# Public_CPU_IO.net
KiCad netlist of a schematic drawn in Altium Designer
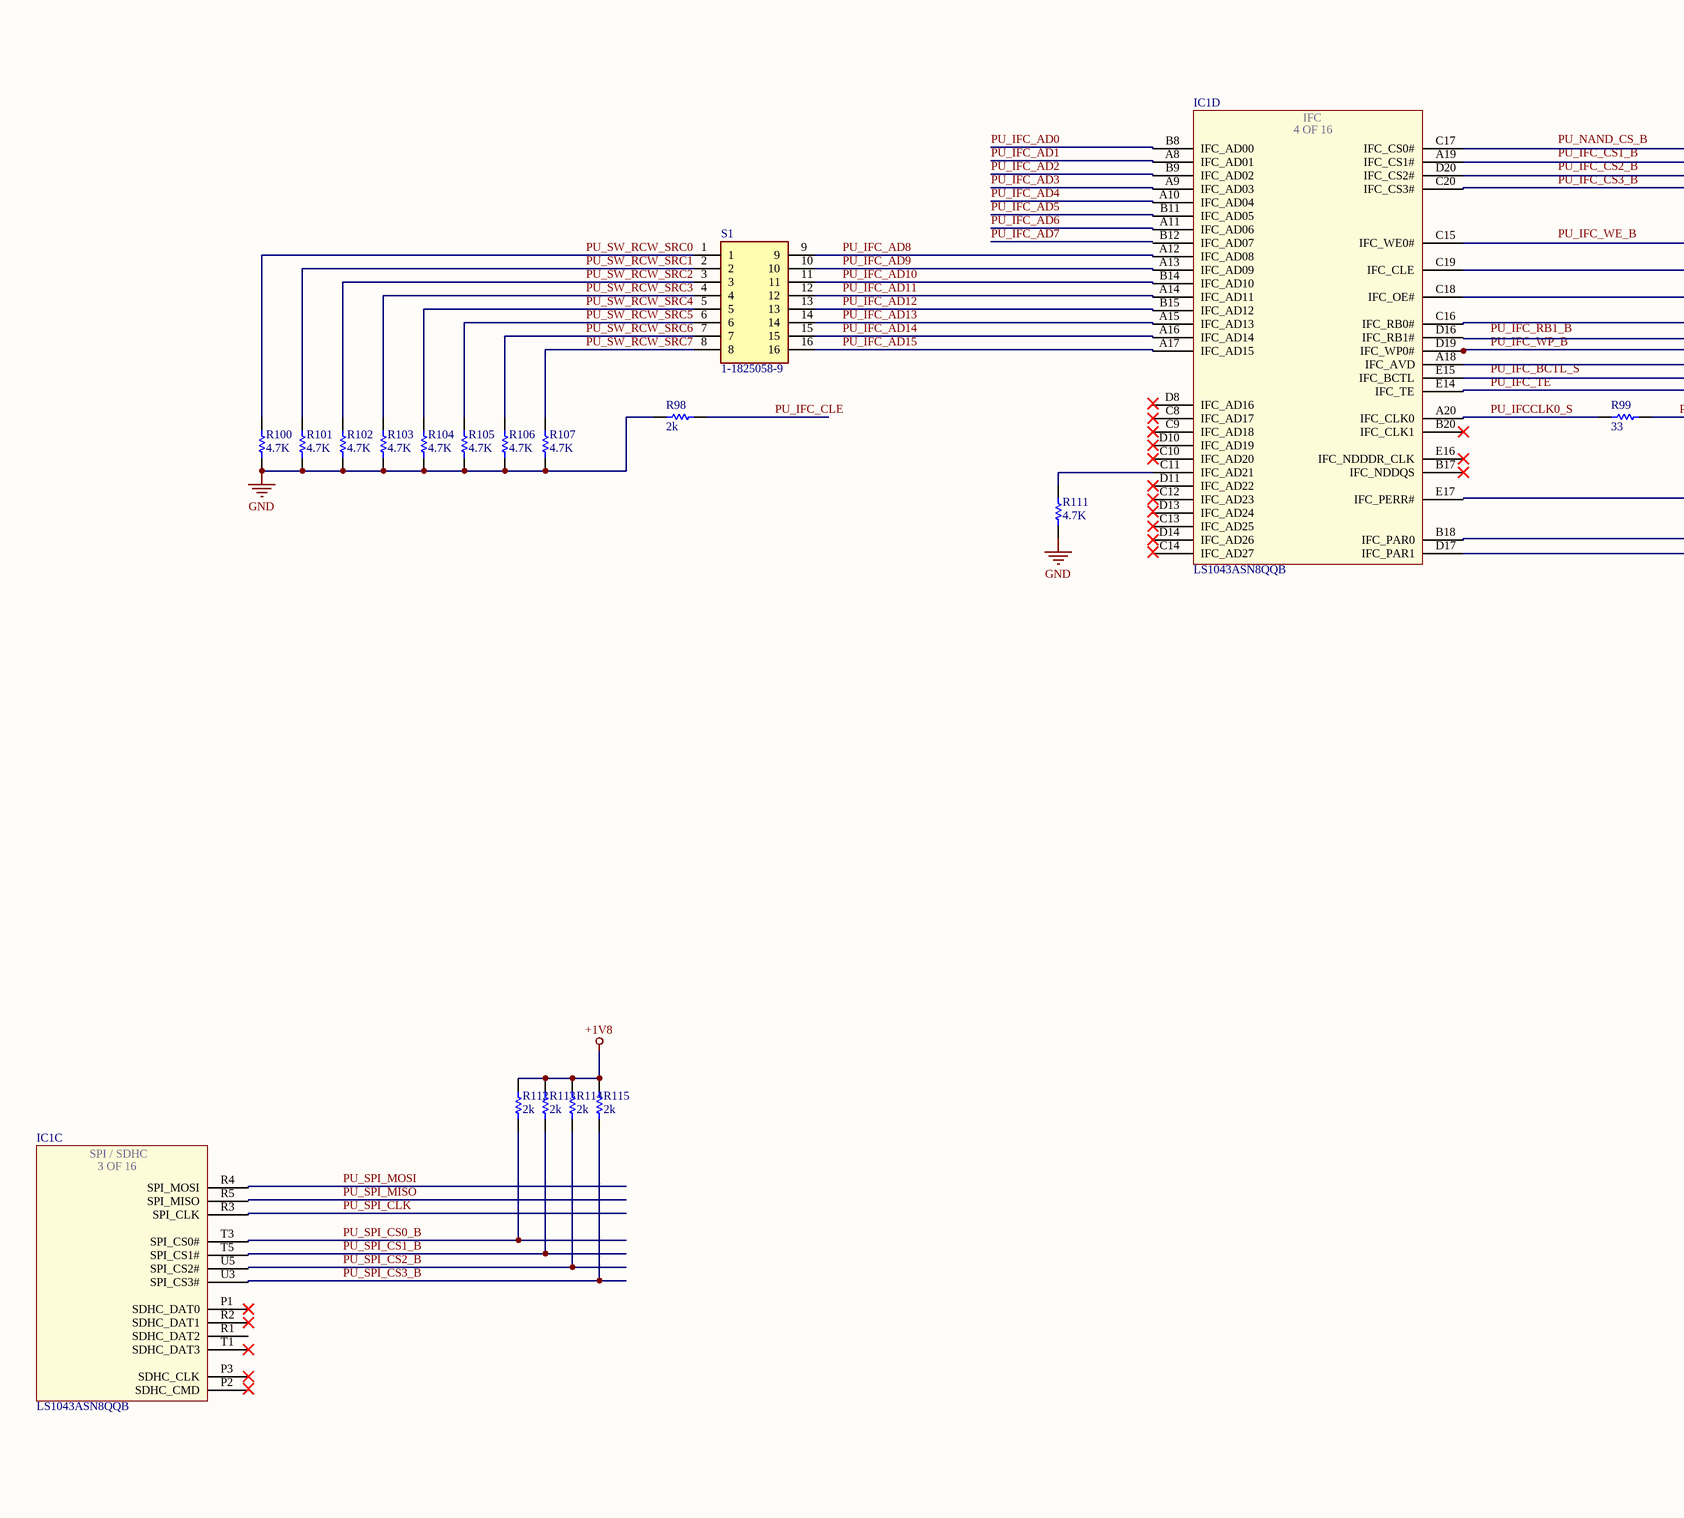
[diagram p0: Public_CPU_IO.SchDoc, left]
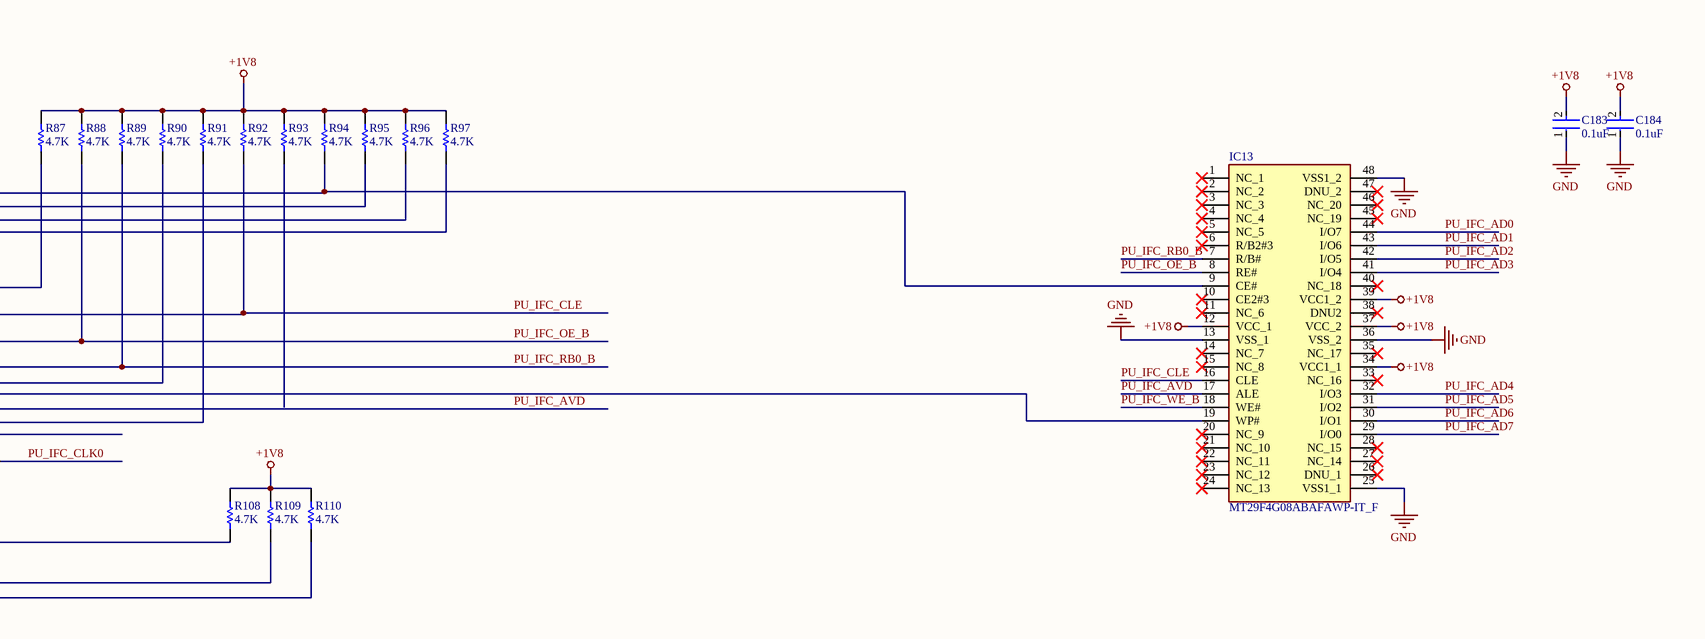
[diagram p1: Public_CPU_IO.SchDoc, right]

(export (version "E")
  (design (tool "Eeschema 10.0.6"))
  (components
    (comp (ref "C183")
      (value "0.1uF")
      (footprint "FP-GRM15-MFG")
      (description "CAP CER 0.1UF 16V X7R 0402")
      (fields (field (name "MANUFACTURER PART NUMBER") "GRM155R71C104KA88D") (field (name "TOLERANCE") "10%"))
      (libsource (lib "Altium Content Vault") (part "236180d848d6139a670b325ea6854c9"))
    )
    (comp (ref "C184")
      (value "0.1uF")
      (footprint "FP-GRM15-MFG")
      (description "CAP CER 0.1UF 16V X7R 0402")
      (fields (field (name "MANUFACTURER PART NUMBER") "GRM155R71C104KA88D") (field (name "TOLERANCE") "10%"))
      (libsource (lib "Altium Content Vault") (part "236180d848d6139a670b325ea6854c9"))
    )
    (comp (ref "IC1")
      (value "LS1043ASN8QQB")
      (footprint "SamacSys:BGA780C80P28X28_2300X2300X261")
      (description "Integrated Circuit")
      (fields (field (name "MOUSER PART NUMBER") "771-LS1043ASN8QQB"))
      (libsource (lib "SamacSys") (part "LS1043ASN8QQB"))
    )
    (comp (ref "IC13")
      (value "MT29F4G08ABAFAWP-IT_F")
      (footprint "SamacSys:SOP50P2000X120-48N")
      (description "Integrated Circuit")
      (fields
        (field (name "MANUFACTURER_PART_NUMBER") "MT29F4G08ABAFAWP-IT:F")
        (field (name "MOUSER PART NUMBER") "340-371016-TRAY")
      )
      (libsource (lib "*") (part "MT29F4G08ABAFAWP-IT_F"))
    )
    (comp (ref "R87")
      (value "4.7K")
      (footprint "RESC1005X40X25LL05T05")
      (description "Chip Resistor, 4.7 KOhm, +/- 1%, 0.1 W, -55 to 155 degC, 0402 (1005 Metric), RoHS, Tape and Reel")
      (fields (field (name "TOLERANCE") "1%") (field (name "PARTNUMBER") "ERJ-2RKF4701X"))
      (libsource (lib "Altium Content Vault") (part "RES-2"))
    )
    (comp (ref "R88")
      (value "4.7K")
      (footprint "RESC1005X40X25LL05T05")
      (description "Chip Resistor, 4.7 KOhm, +/- 1%, 0.1 W, -55 to 155 degC, 0402 (1005 Metric), RoHS, Tape and Reel")
      (fields (field (name "TOLERANCE") "1%") (field (name "PARTNUMBER") "ERJ-2RKF4701X"))
      (libsource (lib "Altium Content Vault") (part "RES-2"))
    )
    (comp (ref "R89")
      (value "4.7K")
      (footprint "RESC1005X40X25LL05T05")
      (description "Chip Resistor, 4.7 KOhm, +/- 1%, 0.1 W, -55 to 155 degC, 0402 (1005 Metric), RoHS, Tape and Reel")
      (fields (field (name "TOLERANCE") "1%") (field (name "PARTNUMBER") "ERJ-2RKF4701X"))
      (libsource (lib "Altium Content Vault") (part "RES-2"))
    )
    (comp (ref "R90")
      (value "4.7K")
      (footprint "RESC1005X40X25LL05T05")
      (description "Chip Resistor, 4.7 KOhm, +/- 1%, 0.1 W, -55 to 155 degC, 0402 (1005 Metric), RoHS, Tape and Reel")
      (fields (field (name "TOLERANCE") "1%") (field (name "PARTNUMBER") "ERJ-2RKF4701X"))
      (libsource (lib "Altium Content Vault") (part "RES-2"))
    )
    (comp (ref "R91")
      (value "4.7K")
      (footprint "RESC1005X40X25LL05T05")
      (description "Chip Resistor, 4.7 KOhm, +/- 1%, 0.1 W, -55 to 155 degC, 0402 (1005 Metric), RoHS, Tape and Reel")
      (fields (field (name "TOLERANCE") "1%") (field (name "PARTNUMBER") "ERJ-2RKF4701X"))
      (libsource (lib "Altium Content Vault") (part "RES-2"))
    )
    (comp (ref "R92")
      (value "4.7K")
      (footprint "RESC1005X40X25LL05T05")
      (description "Chip Resistor, 4.7 KOhm, +/- 1%, 0.1 W, -55 to 155 degC, 0402 (1005 Metric), RoHS, Tape and Reel")
      (fields (field (name "TOLERANCE") "1%") (field (name "PARTNUMBER") "ERJ-2RKF4701X"))
      (libsource (lib "Altium Content Vault") (part "RES-2"))
    )
    (comp (ref "R93")
      (value "4.7K")
      (footprint "RESC1005X40X25LL05T05")
      (description "Chip Resistor, 4.7 KOhm, +/- 1%, 0.1 W, -55 to 155 degC, 0402 (1005 Metric), RoHS, Tape and Reel")
      (fields (field (name "TOLERANCE") "1%") (field (name "PARTNUMBER") "ERJ-2RKF4701X"))
      (libsource (lib "Altium Content Vault") (part "RES-2"))
    )
    (comp (ref "R94")
      (value "4.7K")
      (footprint "RESC1005X40X25LL05T05")
      (description "Chip Resistor, 4.7 KOhm, +/- 1%, 0.1 W, -55 to 155 degC, 0402 (1005 Metric), RoHS, Tape and Reel")
      (fields (field (name "TOLERANCE") "1%") (field (name "PARTNUMBER") "ERJ-2RKF4701X"))
      (libsource (lib "Altium Content Vault") (part "RES-2"))
    )
    (comp (ref "R95")
      (value "4.7K")
      (footprint "RESC1005X40X25LL05T05")
      (description "Chip Resistor, 4.7 KOhm, +/- 1%, 0.1 W, -55 to 155 degC, 0402 (1005 Metric), RoHS, Tape and Reel")
      (fields (field (name "TOLERANCE") "1%") (field (name "PARTNUMBER") "ERJ-2RKF4701X"))
      (libsource (lib "Altium Content Vault") (part "RES-2"))
    )
    (comp (ref "R96")
      (value "4.7K")
      (footprint "RESC1005X40X25LL05T05")
      (description "Chip Resistor, 4.7 KOhm, +/- 1%, 0.1 W, -55 to 155 degC, 0402 (1005 Metric), RoHS, Tape and Reel")
      (fields (field (name "TOLERANCE") "1%") (field (name "PARTNUMBER") "ERJ-2RKF4701X"))
      (libsource (lib "Altium Content Vault") (part "RES-2"))
    )
    (comp (ref "R97")
      (value "4.7K")
      (footprint "RESC1005X40X25LL05T05")
      (description "Chip Resistor, 4.7 KOhm, +/- 1%, 0.1 W, -55 to 155 degC, 0402 (1005 Metric), RoHS, Tape and Reel")
      (fields (field (name "TOLERANCE") "1%") (field (name "PARTNUMBER") "ERJ-2RKF4701X"))
      (libsource (lib "Altium Content Vault") (part "RES-2"))
    )
    (comp (ref "R98")
      (value "2k")
      (footprint "RESC1005X40X25NL05T05")
      (description "Chip Resistor, 2 KOhm, +/- 1%, 100 mW, -55 to 155 degC, 0402 (1005 Metric), RoHS, Tape and Reel")
      (fields (field (name "MANUFACTURER") "Basic Passives") (field (name "TOLERANCE") "1%"))
      (libsource (lib "Altium Content Vault") (part "RES-2"))
    )
    (comp (ref "R99")
      (value "33")
      (footprint "RESC1005X40X25LL05T05")
      (fields (field (name "MANUFACTURER") "Panasonic") (field (name "PART NUMBER") "ERJ2RKF33R0X"))
      (libsource (lib "Altium Content Vault") (part "RES"))
    )
    (comp (ref "R100")
      (value "4.7K")
      (footprint "RESC1005X40X25LL05T05")
      (description "Chip Resistor, 4.7 KOhm, +/- 1%, 0.1 W, -55 to 155 degC, 0402 (1005 Metric), RoHS, Tape and Reel")
      (fields (field (name "TOLERANCE") "1%") (field (name "PARTNUMBER") "ERJ-2RKF4701X"))
      (libsource (lib "Altium Content Vault") (part "RES-2"))
    )
    (comp (ref "R101")
      (value "4.7K")
      (footprint "RESC1005X40X25LL05T05")
      (description "Chip Resistor, 4.7 KOhm, +/- 1%, 0.1 W, -55 to 155 degC, 0402 (1005 Metric), RoHS, Tape and Reel")
      (fields (field (name "TOLERANCE") "1%") (field (name "PARTNUMBER") "ERJ-2RKF4701X"))
      (libsource (lib "Altium Content Vault") (part "RES-2"))
    )
    (comp (ref "R102")
      (value "4.7K")
      (footprint "RESC1005X40X25LL05T05")
      (description "Chip Resistor, 4.7 KOhm, +/- 1%, 0.1 W, -55 to 155 degC, 0402 (1005 Metric), RoHS, Tape and Reel")
      (fields (field (name "TOLERANCE") "1%") (field (name "PARTNUMBER") "ERJ-2RKF4701X"))
      (libsource (lib "Altium Content Vault") (part "RES-2"))
    )
    (comp (ref "R103")
      (value "4.7K")
      (footprint "RESC1005X40X25LL05T05")
      (description "Chip Resistor, 4.7 KOhm, +/- 1%, 0.1 W, -55 to 155 degC, 0402 (1005 Metric), RoHS, Tape and Reel")
      (fields (field (name "TOLERANCE") "1%") (field (name "PARTNUMBER") "ERJ-2RKF4701X"))
      (libsource (lib "Altium Content Vault") (part "RES-2"))
    )
    (comp (ref "R104")
      (value "4.7K")
      (footprint "RESC1005X40X25LL05T05")
      (description "Chip Resistor, 4.7 KOhm, +/- 1%, 0.1 W, -55 to 155 degC, 0402 (1005 Metric), RoHS, Tape and Reel")
      (fields (field (name "TOLERANCE") "1%") (field (name "PARTNUMBER") "ERJ-2RKF4701X"))
      (libsource (lib "Altium Content Vault") (part "RES-2"))
    )
    (comp (ref "R105")
      (value "4.7K")
      (footprint "RESC1005X40X25LL05T05")
      (description "Chip Resistor, 4.7 KOhm, +/- 1%, 0.1 W, -55 to 155 degC, 0402 (1005 Metric), RoHS, Tape and Reel")
      (fields (field (name "TOLERANCE") "1%") (field (name "PARTNUMBER") "ERJ-2RKF4701X"))
      (libsource (lib "Altium Content Vault") (part "RES-2"))
    )
    (comp (ref "R106")
      (value "4.7K")
      (footprint "RESC1005X40X25LL05T05")
      (description "Chip Resistor, 4.7 KOhm, +/- 1%, 0.1 W, -55 to 155 degC, 0402 (1005 Metric), RoHS, Tape and Reel")
      (fields (field (name "TOLERANCE") "1%") (field (name "PARTNUMBER") "ERJ-2RKF4701X"))
      (libsource (lib "Altium Content Vault") (part "RES-2"))
    )
    (comp (ref "R107")
      (value "4.7K")
      (footprint "RESC1005X40X25LL05T05")
      (description "Chip Resistor, 4.7 KOhm, +/- 1%, 0.1 W, -55 to 155 degC, 0402 (1005 Metric), RoHS, Tape and Reel")
      (fields (field (name "TOLERANCE") "1%") (field (name "PARTNUMBER") "ERJ-2RKF4701X"))
      (libsource (lib "Altium Content Vault") (part "RES-2"))
    )
    (comp (ref "R108")
      (value "4.7K")
      (footprint "RESC1005X40X25LL05T05")
      (description "Chip Resistor, 4.7 KOhm, +/- 1%, 0.1 W, -55 to 155 degC, 0402 (1005 Metric), RoHS, Tape and Reel")
      (fields (field (name "TOLERANCE") "1%") (field (name "PARTNUMBER") "ERJ-2RKF4701X"))
      (libsource (lib "Altium Content Vault") (part "RES-2"))
    )
    (comp (ref "R109")
      (value "4.7K")
      (footprint "RESC1005X40X25LL05T05")
      (description "Chip Resistor, 4.7 KOhm, +/- 1%, 0.1 W, -55 to 155 degC, 0402 (1005 Metric), RoHS, Tape and Reel")
      (fields (field (name "TOLERANCE") "1%") (field (name "PARTNUMBER") "ERJ-2RKF4701X"))
      (libsource (lib "Altium Content Vault") (part "RES-2"))
    )
    (comp (ref "R110")
      (value "4.7K")
      (footprint "RESC1005X40X25LL05T05")
      (description "Chip Resistor, 4.7 KOhm, +/- 1%, 0.1 W, -55 to 155 degC, 0402 (1005 Metric), RoHS, Tape and Reel")
      (fields (field (name "TOLERANCE") "1%") (field (name "PARTNUMBER") "ERJ-2RKF4701X"))
      (libsource (lib "Altium Content Vault") (part "RES-2"))
    )
    (comp (ref "R111")
      (value "4.7K")
      (footprint "RESC1005X40X25LL05T05")
      (description "Chip Resistor, 4.7 KOhm, +/- 1%, 0.1 W, -55 to 155 degC, 0402 (1005 Metric), RoHS, Tape and Reel")
      (fields (field (name "TOLERANCE") "1%") (field (name "PARTNUMBER") "ERJ-2RKF4701X"))
      (libsource (lib "Altium Content Vault") (part "RES-2"))
    )
    (comp (ref "R112")
      (value "2k")
      (footprint "RESC1005X40X25NL05T05")
      (description "Chip Resistor, 2 KOhm, +/- 1%, 100 mW, -55 to 155 degC, 0402 (1005 Metric), RoHS, Tape and Reel")
      (fields (field (name "MANUFACTURER") "Basic Passives") (field (name "TOLERANCE") "1%"))
      (libsource (lib "Altium Content Vault") (part "RES-2"))
    )
    (comp (ref "R113")
      (value "2k")
      (footprint "RESC1005X40X25NL05T05")
      (description "Chip Resistor, 2 KOhm, +/- 1%, 100 mW, -55 to 155 degC, 0402 (1005 Metric), RoHS, Tape and Reel")
      (fields (field (name "MANUFACTURER") "Basic Passives") (field (name "TOLERANCE") "1%"))
      (libsource (lib "Altium Content Vault") (part "RES-2"))
    )
    (comp (ref "R114")
      (value "2k")
      (footprint "RESC1005X40X25NL05T05")
      (description "Chip Resistor, 2 KOhm, +/- 1%, 100 mW, -55 to 155 degC, 0402 (1005 Metric), RoHS, Tape and Reel")
      (fields (field (name "MANUFACTURER") "Basic Passives") (field (name "TOLERANCE") "1%"))
      (libsource (lib "Altium Content Vault") (part "RES-2"))
    )
    (comp (ref "R115")
      (value "2k")
      (footprint "RESC1005X40X25NL05T05")
      (description "Chip Resistor, 2 KOhm, +/- 1%, 100 mW, -55 to 155 degC, 0402 (1005 Metric), RoHS, Tape and Reel")
      (fields (field (name "MANUFACTURER") "Basic Passives") (field (name "TOLERANCE") "1%"))
      (libsource (lib "Altium Content Vault") (part "RES-2"))
    )
    (comp (ref "S1")
      (value "1-1825058-9")
      (footprint "SamacSys:118250589")
      (description "Switch")
      (libsource (lib "*") (part "1-1825058-9"))
    )
  )
  (nets
    (net (code "1") (name "+1V8") (class "Default")
      (node (ref "C183") (pin "2") (pinfunction "2_2") (pintype "passive"))
      (node (ref "C184") (pin "2") (pinfunction "2_2") (pintype "passive"))
      (node (ref "IC13") (pin "12") (pinfunction "VCC_1_12") (pintype "passive"))
      (node (ref "IC13") (pin "34") (pinfunction "VCC1_1_34") (pintype "passive"))
      (node (ref "IC13") (pin "37") (pinfunction "VCC_2_37") (pintype "passive"))
      (node (ref "IC13") (pin "39") (pinfunction "VCC1_2_39") (pintype "passive"))
      (node (ref "R108") (pin "2") (pinfunction "2_2") (pintype "passive"))
      (node (ref "R109") (pin "2") (pinfunction "2_2") (pintype "passive"))
      (node (ref "R110") (pin "2") (pinfunction "2_2") (pintype "passive"))
      (node (ref "R112") (pin "1") (pinfunction "1_1") (pintype "passive"))
      (node (ref "R113") (pin "1") (pinfunction "1_1") (pintype "passive"))
      (node (ref "R114") (pin "1") (pinfunction "1_1") (pintype "passive"))
      (node (ref "R115") (pin "1") (pinfunction "1_1") (pintype "passive"))
      (node (ref "R87") (pin "2") (pinfunction "2_2") (pintype "passive"))
      (node (ref "R88") (pin "2") (pinfunction "2_2") (pintype "passive"))
      (node (ref "R89") (pin "2") (pinfunction "2_2") (pintype "passive"))
      (node (ref "R90") (pin "2") (pinfunction "2_2") (pintype "passive"))
      (node (ref "R91") (pin "2") (pinfunction "2_2") (pintype "passive"))
      (node (ref "R92") (pin "2") (pinfunction "2_2") (pintype "passive"))
      (node (ref "R93") (pin "2") (pinfunction "2_2") (pintype "passive"))
      (node (ref "R94") (pin "2") (pinfunction "2_2") (pintype "passive"))
      (node (ref "R95") (pin "2") (pinfunction "2_2") (pintype "passive"))
      (node (ref "R96") (pin "2") (pinfunction "2_2") (pintype "passive"))
      (node (ref "R97") (pin "2") (pinfunction "2_2") (pintype "passive"))
    )
    (net (code "2") (name "/PU_IFCCLK0_S") (class "Default")
      (node (ref "IC1") (pin "A20") (pinfunction "IFC_CLK0_A20") (pintype "passive"))
      (node (ref "R99") (pin "1") (pinfunction "1_1") (pintype "passive"))
    )
    (net (code "3") (name "/PU_IFC_AD0") (class "Default")
      (node (ref "IC1") (pin "B8") (pinfunction "IFC_AD00_B8") (pintype "passive"))
      (node (ref "IC13") (pin "44") (pinfunction "I/O7_44") (pintype "passive"))
    )
    (net (code "4") (name "/PU_IFC_AD1") (class "Default")
      (node (ref "IC1") (pin "A8") (pinfunction "IFC_AD01_A8") (pintype "passive"))
      (node (ref "IC13") (pin "43") (pinfunction "I/O6_43") (pintype "passive"))
    )
    (net (code "5") (name "/PU_IFC_AD2") (class "Default")
      (node (ref "IC1") (pin "B9") (pinfunction "IFC_AD02_B9") (pintype "passive"))
      (node (ref "IC13") (pin "42") (pinfunction "I/O5_42") (pintype "passive"))
    )
    (net (code "6") (name "/PU_IFC_AD3") (class "Default")
      (node (ref "IC1") (pin "A9") (pinfunction "IFC_AD03_A9") (pintype "passive"))
      (node (ref "IC13") (pin "41") (pinfunction "I/O4_41") (pintype "passive"))
    )
    (net (code "7") (name "/PU_IFC_AD4") (class "Default")
      (node (ref "IC1") (pin "A10") (pinfunction "IFC_AD04_A10") (pintype "passive"))
      (node (ref "IC13") (pin "32") (pinfunction "I/O3_32") (pintype "passive"))
    )
    (net (code "8") (name "/PU_IFC_AD5") (class "Default")
      (node (ref "IC1") (pin "B11") (pinfunction "IFC_AD05_B11") (pintype "passive"))
      (node (ref "IC13") (pin "31") (pinfunction "I/O2_31") (pintype "passive"))
    )
    (net (code "9") (name "/PU_IFC_AD6") (class "Default")
      (node (ref "IC1") (pin "A11") (pinfunction "IFC_AD06_A11") (pintype "passive"))
      (node (ref "IC13") (pin "30") (pinfunction "I/O1_30") (pintype "passive"))
    )
    (net (code "10") (name "/PU_IFC_AD7") (class "Default")
      (node (ref "IC13") (pin "29") (pinfunction "I/O0_29") (pintype "passive"))
    )
    (net (code "11") (name "/PU_IFC_AD8") (class "Default")
      (node (ref "IC1") (pin "A12") (pinfunction "IFC_AD08_A12") (pintype "passive"))
      (node (ref "S1") (pin "9") (pinfunction "9_9") (pintype "passive"))
    )
    (net (code "12") (name "/PU_IFC_AD9") (class "Default")
      (node (ref "IC1") (pin "A13") (pinfunction "IFC_AD09_A13") (pintype "passive"))
      (node (ref "S1") (pin "10") (pinfunction "10_10") (pintype "passive"))
    )
    (net (code "13") (name "/PU_IFC_AD10") (class "Default")
      (node (ref "IC1") (pin "B14") (pinfunction "IFC_AD10_B14") (pintype "passive"))
      (node (ref "S1") (pin "11") (pinfunction "11_11") (pintype "passive"))
    )
    (net (code "14") (name "/PU_IFC_AD11") (class "Default")
      (node (ref "IC1") (pin "A14") (pinfunction "IFC_AD11_A14") (pintype "passive"))
      (node (ref "S1") (pin "12") (pinfunction "12_12") (pintype "passive"))
    )
    (net (code "15") (name "/PU_IFC_AD12") (class "Default")
      (node (ref "IC1") (pin "B15") (pinfunction "IFC_AD12_B15") (pintype "passive"))
      (node (ref "S1") (pin "13") (pinfunction "13_13") (pintype "passive"))
    )
    (net (code "16") (name "/PU_IFC_AD13") (class "Default")
      (node (ref "IC1") (pin "A15") (pinfunction "IFC_AD13_A15") (pintype "passive"))
      (node (ref "S1") (pin "14") (pinfunction "14_14") (pintype "passive"))
    )
    (net (code "17") (name "/PU_IFC_AD14") (class "Default")
      (node (ref "IC1") (pin "A16") (pinfunction "IFC_AD14_A16") (pintype "passive"))
      (node (ref "S1") (pin "15") (pinfunction "15_15") (pintype "passive"))
    )
    (net (code "18") (name "/PU_IFC_AD15") (class "Default")
      (node (ref "IC1") (pin "A17") (pinfunction "IFC_AD15_A17") (pintype "passive"))
      (node (ref "S1") (pin "16") (pinfunction "16_16") (pintype "passive"))
    )
    (net (code "19") (name "/PU_IFC_AVD") (class "Default")
      (node (ref "IC1") (pin "A18") (pinfunction "IFC_AVD_A18") (pintype "passive"))
      (node (ref "IC13") (pin "17") (pinfunction "ALE_17") (pintype "passive"))
    )
    (net (code "21") (name "/PU_IFC_CLE") (class "Default")
      (node (ref "IC1") (pin "C19") (pinfunction "IFC_CLE_C19") (pintype "passive"))
      (node (ref "IC13") (pin "16") (pinfunction "CLE_16") (pintype "passive"))
      (node (ref "R92") (pin "1") (pinfunction "1_1") (pintype "passive"))
      (node (ref "R98") (pin "1") (pinfunction "1_1") (pintype "passive"))
    )
    (net (code "22") (name "/PU_IFC_CLK0") (class "Default")
      (node (ref "R99") (pin "2") (pinfunction "2_2") (pintype "passive"))
    )
    (net (code "25") (name "/PU_IFC_CS3_B") (class "Default")
      (node (ref "IC1") (pin "C20") (pinfunction "IFC_CS3#_C20") (pintype "passive"))
      (node (ref "R97") (pin "1") (pinfunction "1_1") (pintype "passive"))
    )
    (net (code "26") (name "/PU_IFC_OE_B") (class "Default")
      (node (ref "IC1") (pin "C18") (pinfunction "IFC_OE#_C18") (pintype "passive"))
      (node (ref "IC13") (pin "8") (pinfunction "RE#_8") (pintype "passive"))
      (node (ref "R88") (pin "1") (pinfunction "1_1") (pintype "passive"))
    )
    (net (code "27") (name "/PU_IFC_RB0_B") (class "Default")
      (node (ref "IC1") (pin "C16") (pinfunction "IFC_RB0#_C16") (pintype "passive"))
      (node (ref "IC13") (pin "7") (pinfunction "R/B#_7") (pintype "passive"))
      (node (ref "R89") (pin "1") (pinfunction "1_1") (pintype "passive"))
    )
    (net (code "29") (name "/PU_IFC_TE") (class "Default")
      (node (ref "IC1") (pin "E14") (pinfunction "IFC_TE_E14") (pintype "passive"))
    )
    (net (code "30") (name "/PU_IFC_WE_B") (class "Default")
      (node (ref "IC13") (pin "18") (pinfunction "WE#_18") (pintype "passive"))
    )
    (net (code "31") (name "/PU_IFC_WP_B") (class "Default")
      (node (ref "IC1") (pin "D19") (pinfunction "IFC_WP0#_D19") (pintype "passive"))
      (node (ref "IC13") (pin "19") (pinfunction "WP#_19") (pintype "passive"))
    )
    (net (code "33") (name "/PU_SPI_CLK") (class "Default")
      (node (ref "IC1") (pin "R3") (pinfunction "SPI_CLK_R3") (pintype "passive"))
    )
    (net (code "34") (name "/PU_SPI_CS0_B") (class "Default")
      (node (ref "IC1") (pin "T3") (pinfunction "SPI_CS0#_T3") (pintype "passive"))
      (node (ref "R112") (pin "2") (pinfunction "2_2") (pintype "passive"))
    )
    (net (code "35") (name "/PU_SPI_CS1_B") (class "Default")
      (node (ref "IC1") (pin "T5") (pinfunction "SPI_CS1#_T5") (pintype "passive"))
      (node (ref "R113") (pin "2") (pinfunction "2_2") (pintype "passive"))
    )
    (net (code "36") (name "/PU_SPI_CS2_B") (class "Default")
      (node (ref "R114") (pin "2") (pinfunction "2_2") (pintype "passive"))
    )
    (net (code "37") (name "/PU_SPI_CS3_B") (class "Default")
      (node (ref "IC1") (pin "U3") (pinfunction "SPI_CS3#_U3") (pintype "passive"))
      (node (ref "R115") (pin "2") (pinfunction "2_2") (pintype "passive"))
    )
    (net (code "39") (name "/PU_SPI_MOSI") (class "Default")
      (node (ref "IC1") (pin "R4") (pinfunction "SPI_MOSI_R4") (pintype "passive"))
    )
    (net (code "40") (name "/PU_SW_RCW_SRC0") (class "Default")
      (node (ref "R100") (pin "2") (pinfunction "2_2") (pintype "passive"))
      (node (ref "S1") (pin "1") (pinfunction "1_1") (pintype "passive"))
    )
    (net (code "41") (name "/PU_SW_RCW_SRC1") (class "Default")
      (node (ref "R101") (pin "2") (pinfunction "2_2") (pintype "passive"))
      (node (ref "S1") (pin "2") (pinfunction "2_2") (pintype "passive"))
    )
    (net (code "42") (name "/PU_SW_RCW_SRC2") (class "Default")
      (node (ref "R102") (pin "2") (pinfunction "2_2") (pintype "passive"))
      (node (ref "S1") (pin "3") (pinfunction "3_3") (pintype "passive"))
    )
    (net (code "43") (name "/PU_SW_RCW_SRC3") (class "Default")
      (node (ref "R103") (pin "2") (pinfunction "2_2") (pintype "passive"))
      (node (ref "S1") (pin "4") (pinfunction "4_4") (pintype "passive"))
    )
    (net (code "44") (name "/PU_SW_RCW_SRC4") (class "Default")
      (node (ref "R104") (pin "2") (pinfunction "2_2") (pintype "passive"))
      (node (ref "S1") (pin "5") (pinfunction "5_5") (pintype "passive"))
    )
    (net (code "45") (name "/PU_SW_RCW_SRC5") (class "Default")
      (node (ref "R105") (pin "2") (pinfunction "2_2") (pintype "passive"))
      (node (ref "S1") (pin "6") (pinfunction "6_6") (pintype "passive"))
    )
    (net (code "46") (name "/PU_SW_RCW_SRC6") (class "Default")
      (node (ref "R106") (pin "2") (pinfunction "2_2") (pintype "passive"))
      (node (ref "S1") (pin "7") (pinfunction "7_7") (pintype "passive"))
    )
    (net (code "47") (name "/PU_SW_RCW_SRC7") (class "Default")
      (node (ref "R107") (pin "2") (pinfunction "2_2") (pintype "passive"))
      (node (ref "S1") (pin "8") (pinfunction "8_8") (pintype "passive"))
    )
    (net (code "48") (name "GND") (class "Default")
      (node (ref "C183") (pin "1") (pinfunction "1_1") (pintype "passive"))
      (node (ref "C184") (pin "1") (pinfunction "1_1") (pintype "passive"))
      (node (ref "IC13") (pin "13") (pinfunction "VSS_1_13") (pintype "passive"))
      (node (ref "IC13") (pin "25") (pinfunction "VSS1_1_25") (pintype "passive"))
      (node (ref "IC13") (pin "36") (pinfunction "VSS_2_36") (pintype "passive"))
      (node (ref "IC13") (pin "48") (pinfunction "VSS1_2_48") (pintype "passive"))
      (node (ref "R100") (pin "1") (pinfunction "1_1") (pintype "passive"))
      (node (ref "R101") (pin "1") (pinfunction "1_1") (pintype "passive"))
      (node (ref "R102") (pin "1") (pinfunction "1_1") (pintype "passive"))
      (node (ref "R103") (pin "1") (pinfunction "1_1") (pintype "passive"))
      (node (ref "R104") (pin "1") (pinfunction "1_1") (pintype "passive"))
      (node (ref "R105") (pin "1") (pinfunction "1_1") (pintype "passive"))
      (node (ref "R106") (pin "1") (pinfunction "1_1") (pintype "passive"))
      (node (ref "R107") (pin "1") (pinfunction "1_1") (pintype "passive"))
      (node (ref "R111") (pin "1") (pinfunction "1_1") (pintype "passive"))
      (node (ref "R98") (pin "2") (pinfunction "2_2") (pintype "passive"))
    )
    (net (code "49") (name "Net-(IC1D-IFC_AD21)") (class "Default")
      (node (ref "IC1") (pin "C11") (pinfunction "IFC_AD21_C11") (pintype "passive"))
      (node (ref "R111") (pin "2") (pinfunction "2_2") (pintype "passive"))
    )
    (net (code "50") (name "Net-(IC1D-IFC_BCTL)") (class "Default")
      (node (ref "IC1") (pin "E15") (pinfunction "IFC_BCTL_E15") (pintype "passive"))
      (node (ref "R91") (pin "1") (pinfunction "1_1") (pintype "passive"))
    )
    (net (code "51") (name "Net-(IC1D-IFC_CS1#)") (class "Default")
      (node (ref "IC1") (pin "A19") (pinfunction "IFC_CS1#_A19") (pintype "passive"))
      (node (ref "R95") (pin "1") (pinfunction "1_1") (pintype "passive"))
    )
    (net (code "52") (name "Net-(IC1D-IFC_CS2#)") (class "Default")
      (node (ref "IC1") (pin "D20") (pinfunction "IFC_CS2#_D20") (pintype "passive"))
      (node (ref "R96") (pin "1") (pinfunction "1_1") (pintype "passive"))
    )
    (net (code "53") (name "Net-(IC1D-IFC_PAR0)") (class "Default")
      (node (ref "IC1") (pin "B18") (pinfunction "IFC_PAR0_B18") (pintype "passive"))
      (node (ref "R109") (pin "1") (pinfunction "1_1") (pintype "passive"))
    )
    (net (code "54") (name "Net-(IC1D-IFC_PAR1)") (class "Default")
      (node (ref "IC1") (pin "D17") (pinfunction "IFC_PAR1_D17") (pintype "passive"))
      (node (ref "R110") (pin "1") (pinfunction "1_1") (pintype "passive"))
    )
    (net (code "55") (name "Net-(IC1D-IFC_WE0#)") (class "Default")
      (node (ref "IC1") (pin "C15") (pinfunction "IFC_WE0#_C15") (pintype "passive"))
      (node (ref "R87") (pin "1") (pinfunction "1_1") (pintype "passive"))
    )
    (net (code "56") (name "Net-(IC13-CE#)") (class "Default")
      (node (ref "IC1") (pin "C17") (pinfunction "IFC_CS0#_C17") (pintype "passive"))
      (node (ref "IC13") (pin "9") (pinfunction "CE#_9") (pintype "passive"))
      (node (ref "R94") (pin "1") (pinfunction "1_1") (pintype "passive"))
    )
    (net (code "57") (name "unconnected-(IC1C-SDHC_CLK-PadP3)") (class "Default")
      (node (ref "IC1") (pin "P3") (pinfunction "SDHC_CLK_P3") (pintype "passive+no_connect"))
    )
    (net (code "58") (name "unconnected-(IC1C-SDHC_CMD-PadP2)") (class "Default")
      (node (ref "IC1") (pin "P2") (pinfunction "SDHC_CMD_P2") (pintype "passive"))
    )
    (net (code "59") (name "unconnected-(IC1C-SDHC_DAT0-PadP1)") (class "Default")
      (node (ref "IC1") (pin "P1") (pinfunction "SDHC_DAT0_P1") (pintype "passive+no_connect"))
    )
    (net (code "60") (name "unconnected-(IC1C-SDHC_DAT1-PadR2)") (class "Default")
      (node (ref "IC1") (pin "R2") (pinfunction "SDHC_DAT1_R2") (pintype "passive+no_connect"))
    )
    (net (code "61") (name "unconnected-(IC1C-SDHC_DAT2-PadR1)") (class "Default")
      (node (ref "IC1") (pin "R1") (pinfunction "SDHC_DAT2_R1") (pintype "passive"))
    )
    (net (code "62") (name "unconnected-(IC1C-SDHC_DAT3-PadT1)") (class "Default")
      (node (ref "IC1") (pin "T1") (pinfunction "SDHC_DAT3_T1") (pintype "passive+no_connect"))
    )
    (net (code "63") (name "unconnected-(IC1C-SPI_CS2#-PadU5)") (class "Default")
      (node (ref "IC1") (pin "U5") (pinfunction "SPI_CS2#_U5") (pintype "passive"))
    )
    (net (code "64") (name "unconnected-(IC1C-SPI_MISO-PadR5)") (class "Default")
      (node (ref "IC1") (pin "R5") (pinfunction "SPI_MISO_R5") (pintype "passive"))
    )
    (net (code "65") (name "unconnected-(IC1D-IFC_AD07-PadB12)") (class "Default")
      (node (ref "IC1") (pin "B12") (pinfunction "IFC_AD07_B12") (pintype "passive"))
    )
    (net (code "66") (name "unconnected-(IC1D-IFC_AD16-PadD8)") (class "Default")
      (node (ref "IC1") (pin "D8") (pinfunction "IFC_AD16_D8") (pintype "passive"))
    )
    (net (code "67") (name "unconnected-(IC1D-IFC_AD17-PadC8)") (class "Default")
      (node (ref "IC1") (pin "C8") (pinfunction "IFC_AD17_C8") (pintype "passive+no_connect"))
    )
    (net (code "68") (name "unconnected-(IC1D-IFC_AD18-PadC9)") (class "Default")
      (node (ref "IC1") (pin "C9") (pinfunction "IFC_AD18_C9") (pintype "passive+no_connect"))
    )
    (net (code "69") (name "unconnected-(IC1D-IFC_AD19-PadD10)") (class "Default")
      (node (ref "IC1") (pin "D10") (pinfunction "IFC_AD19_D10") (pintype "passive+no_connect"))
    )
    (net (code "70") (name "unconnected-(IC1D-IFC_AD20-PadC10)") (class "Default")
      (node (ref "IC1") (pin "C10") (pinfunction "IFC_AD20_C10") (pintype "passive+no_connect"))
    )
    (net (code "71") (name "unconnected-(IC1D-IFC_AD22-PadD11)") (class "Default")
      (node (ref "IC1") (pin "D11") (pinfunction "IFC_AD22_D11") (pintype "passive+no_connect"))
    )
    (net (code "72") (name "unconnected-(IC1D-IFC_AD23-PadC12)") (class "Default")
      (node (ref "IC1") (pin "C12") (pinfunction "IFC_AD23_C12") (pintype "passive+no_connect"))
    )
    (net (code "73") (name "unconnected-(IC1D-IFC_AD24-PadD13)") (class "Default")
      (node (ref "IC1") (pin "D13") (pinfunction "IFC_AD24_D13") (pintype "passive"))
    )
    (net (code "74") (name "unconnected-(IC1D-IFC_AD25-PadC13)") (class "Default")
      (node (ref "IC1") (pin "C13") (pinfunction "IFC_AD25_C13") (pintype "passive+no_connect"))
    )
    (net (code "75") (name "unconnected-(IC1D-IFC_AD26-PadD14)") (class "Default")
      (node (ref "IC1") (pin "D14") (pinfunction "IFC_AD26_D14") (pintype "passive+no_connect"))
    )
    (net (code "76") (name "unconnected-(IC1D-IFC_AD27-PadC14)") (class "Default")
      (node (ref "IC1") (pin "C14") (pinfunction "IFC_AD27_C14") (pintype "passive"))
    )
    (net (code "77") (name "unconnected-(IC1D-IFC_CLK1-PadB20)") (class "Default")
      (node (ref "IC1") (pin "B20") (pinfunction "IFC_CLK1_B20") (pintype "passive+no_connect"))
    )
    (net (code "78") (name "unconnected-(IC1D-IFC_NDDDR_CLK-PadE16)") (class "Default")
      (node (ref "IC1") (pin "E16") (pinfunction "IFC_NDDDR_CLK_E16") (pintype "passive+no_connect"))
    )
    (net (code "79") (name "unconnected-(IC1D-IFC_NDDQS-PadB17)") (class "Default")
      (node (ref "IC1") (pin "B17") (pinfunction "IFC_NDDQS_B17") (pintype "passive+no_connect"))
    )
    (net (code "80") (name "unconnected-(IC1D-IFC_PERR#-PadE17)") (class "Default")
      (node (ref "IC1") (pin "E17") (pinfunction "IFC_PERR#_E17") (pintype "passive"))
    )
    (net (code "81") (name "unconnected-(IC1D-IFC_RB1#-PadD16)") (class "Default")
      (node (ref "IC1") (pin "D16") (pinfunction "IFC_RB1#_D16") (pintype "passive"))
    )
    (net (code "82") (name "unconnected-(IC13-CE2#3-Pad10)") (class "Default")
      (node (ref "IC13") (pin "10") (pinfunction "CE2#3_10") (pintype "passive+no_connect"))
    )
    (net (code "83") (name "unconnected-(IC13-DNU2-Pad38)") (class "Default")
      (node (ref "IC13") (pin "38") (pinfunction "DNU2_38") (pintype "passive+no_connect"))
    )
    (net (code "84") (name "unconnected-(IC13-DNU_1-Pad26)") (class "Default")
      (node (ref "IC13") (pin "26") (pinfunction "DNU_1_26") (pintype "passive+no_connect"))
    )
    (net (code "85") (name "unconnected-(IC13-DNU_2-Pad47)") (class "Default")
      (node (ref "IC13") (pin "47") (pinfunction "DNU_2_47") (pintype "passive+no_connect"))
    )
    (net (code "86") (name "unconnected-(IC13-NC_1-Pad1)") (class "Default")
      (node (ref "IC13") (pin "1") (pinfunction "NC_1_1") (pintype "passive+no_connect"))
    )
    (net (code "87") (name "unconnected-(IC13-NC_2-Pad2)") (class "Default")
      (node (ref "IC13") (pin "2") (pinfunction "NC_2_2") (pintype "passive+no_connect"))
    )
    (net (code "88") (name "unconnected-(IC13-NC_3-Pad3)") (class "Default")
      (node (ref "IC13") (pin "3") (pinfunction "NC_3_3") (pintype "passive+no_connect"))
    )
    (net (code "89") (name "unconnected-(IC13-NC_4-Pad4)") (class "Default")
      (node (ref "IC13") (pin "4") (pinfunction "NC_4_4") (pintype "passive+no_connect"))
    )
    (net (code "90") (name "unconnected-(IC13-NC_5-Pad5)") (class "Default")
      (node (ref "IC13") (pin "5") (pinfunction "NC_5_5") (pintype "passive+no_connect"))
    )
    (net (code "91") (name "unconnected-(IC13-NC_6-Pad11)") (class "Default")
      (node (ref "IC13") (pin "11") (pinfunction "NC_6_11") (pintype "passive+no_connect"))
    )
    (net (code "92") (name "unconnected-(IC13-NC_7-Pad14)") (class "Default")
      (node (ref "IC13") (pin "14") (pinfunction "NC_7_14") (pintype "passive+no_connect"))
    )
    (net (code "93") (name "unconnected-(IC13-NC_8-Pad15)") (class "Default")
      (node (ref "IC13") (pin "15") (pinfunction "NC_8_15") (pintype "passive+no_connect"))
    )
    (net (code "94") (name "unconnected-(IC13-NC_9-Pad20)") (class "Default")
      (node (ref "IC13") (pin "20") (pinfunction "NC_9_20") (pintype "passive+no_connect"))
    )
    (net (code "95") (name "unconnected-(IC13-NC_10-Pad21)") (class "Default")
      (node (ref "IC13") (pin "21") (pinfunction "NC_10_21") (pintype "passive+no_connect"))
    )
    (net (code "96") (name "unconnected-(IC13-NC_11-Pad22)") (class "Default")
      (node (ref "IC13") (pin "22") (pinfunction "NC_11_22") (pintype "passive+no_connect"))
    )
    (net (code "97") (name "unconnected-(IC13-NC_12-Pad23)") (class "Default")
      (node (ref "IC13") (pin "23") (pinfunction "NC_12_23") (pintype "passive+no_connect"))
    )
    (net (code "98") (name "unconnected-(IC13-NC_13-Pad24)") (class "Default")
      (node (ref "IC13") (pin "24") (pinfunction "NC_13_24") (pintype "passive+no_connect"))
    )
    (net (code "99") (name "unconnected-(IC13-NC_14-Pad27)") (class "Default")
      (node (ref "IC13") (pin "27") (pinfunction "NC_14_27") (pintype "passive+no_connect"))
    )
    (net (code "100") (name "unconnected-(IC13-NC_15-Pad28)") (class "Default")
      (node (ref "IC13") (pin "28") (pinfunction "NC_15_28") (pintype "passive+no_connect"))
    )
    (net (code "101") (name "unconnected-(IC13-NC_16-Pad33)") (class "Default")
      (node (ref "IC13") (pin "33") (pinfunction "NC_16_33") (pintype "passive+no_connect"))
    )
    (net (code "102") (name "unconnected-(IC13-NC_17-Pad35)") (class "Default")
      (node (ref "IC13") (pin "35") (pinfunction "NC_17_35") (pintype "passive+no_connect"))
    )
    (net (code "103") (name "unconnected-(IC13-NC_18-Pad40)") (class "Default")
      (node (ref "IC13") (pin "40") (pinfunction "NC_18_40") (pintype "passive+no_connect"))
    )
    (net (code "104") (name "unconnected-(IC13-NC_19-Pad45)") (class "Default")
      (node (ref "IC13") (pin "45") (pinfunction "NC_19_45") (pintype "passive+no_connect"))
    )
    (net (code "105") (name "unconnected-(IC13-NC_20-Pad46)") (class "Default")
      (node (ref "IC13") (pin "46") (pinfunction "NC_20_46") (pintype "passive+no_connect"))
    )
    (net (code "106") (name "unconnected-(IC13-R{slash}B2#3-Pad6)") (class "Default")
      (node (ref "IC13") (pin "6") (pinfunction "R/B2#3_6") (pintype "passive+no_connect"))
    )
    (net (code "107") (name "unconnected-(R90-Pad1)") (class "Default")
      (node (ref "R90") (pin "1") (pinfunction "1_1") (pintype "passive"))
    )
    (net (code "108") (name "unconnected-(R93-Pad1)") (class "Default")
      (node (ref "R93") (pin "1") (pinfunction "1_1") (pintype "passive"))
    )
    (net (code "109") (name "unconnected-(R108-Pad1)") (class "Default")
      (node (ref "R108") (pin "1") (pinfunction "1_1") (pintype "passive"))
    )
  )
)
